# DDS_Module_r1.net
KiCad netlist of a schematic drawn in EAGLE
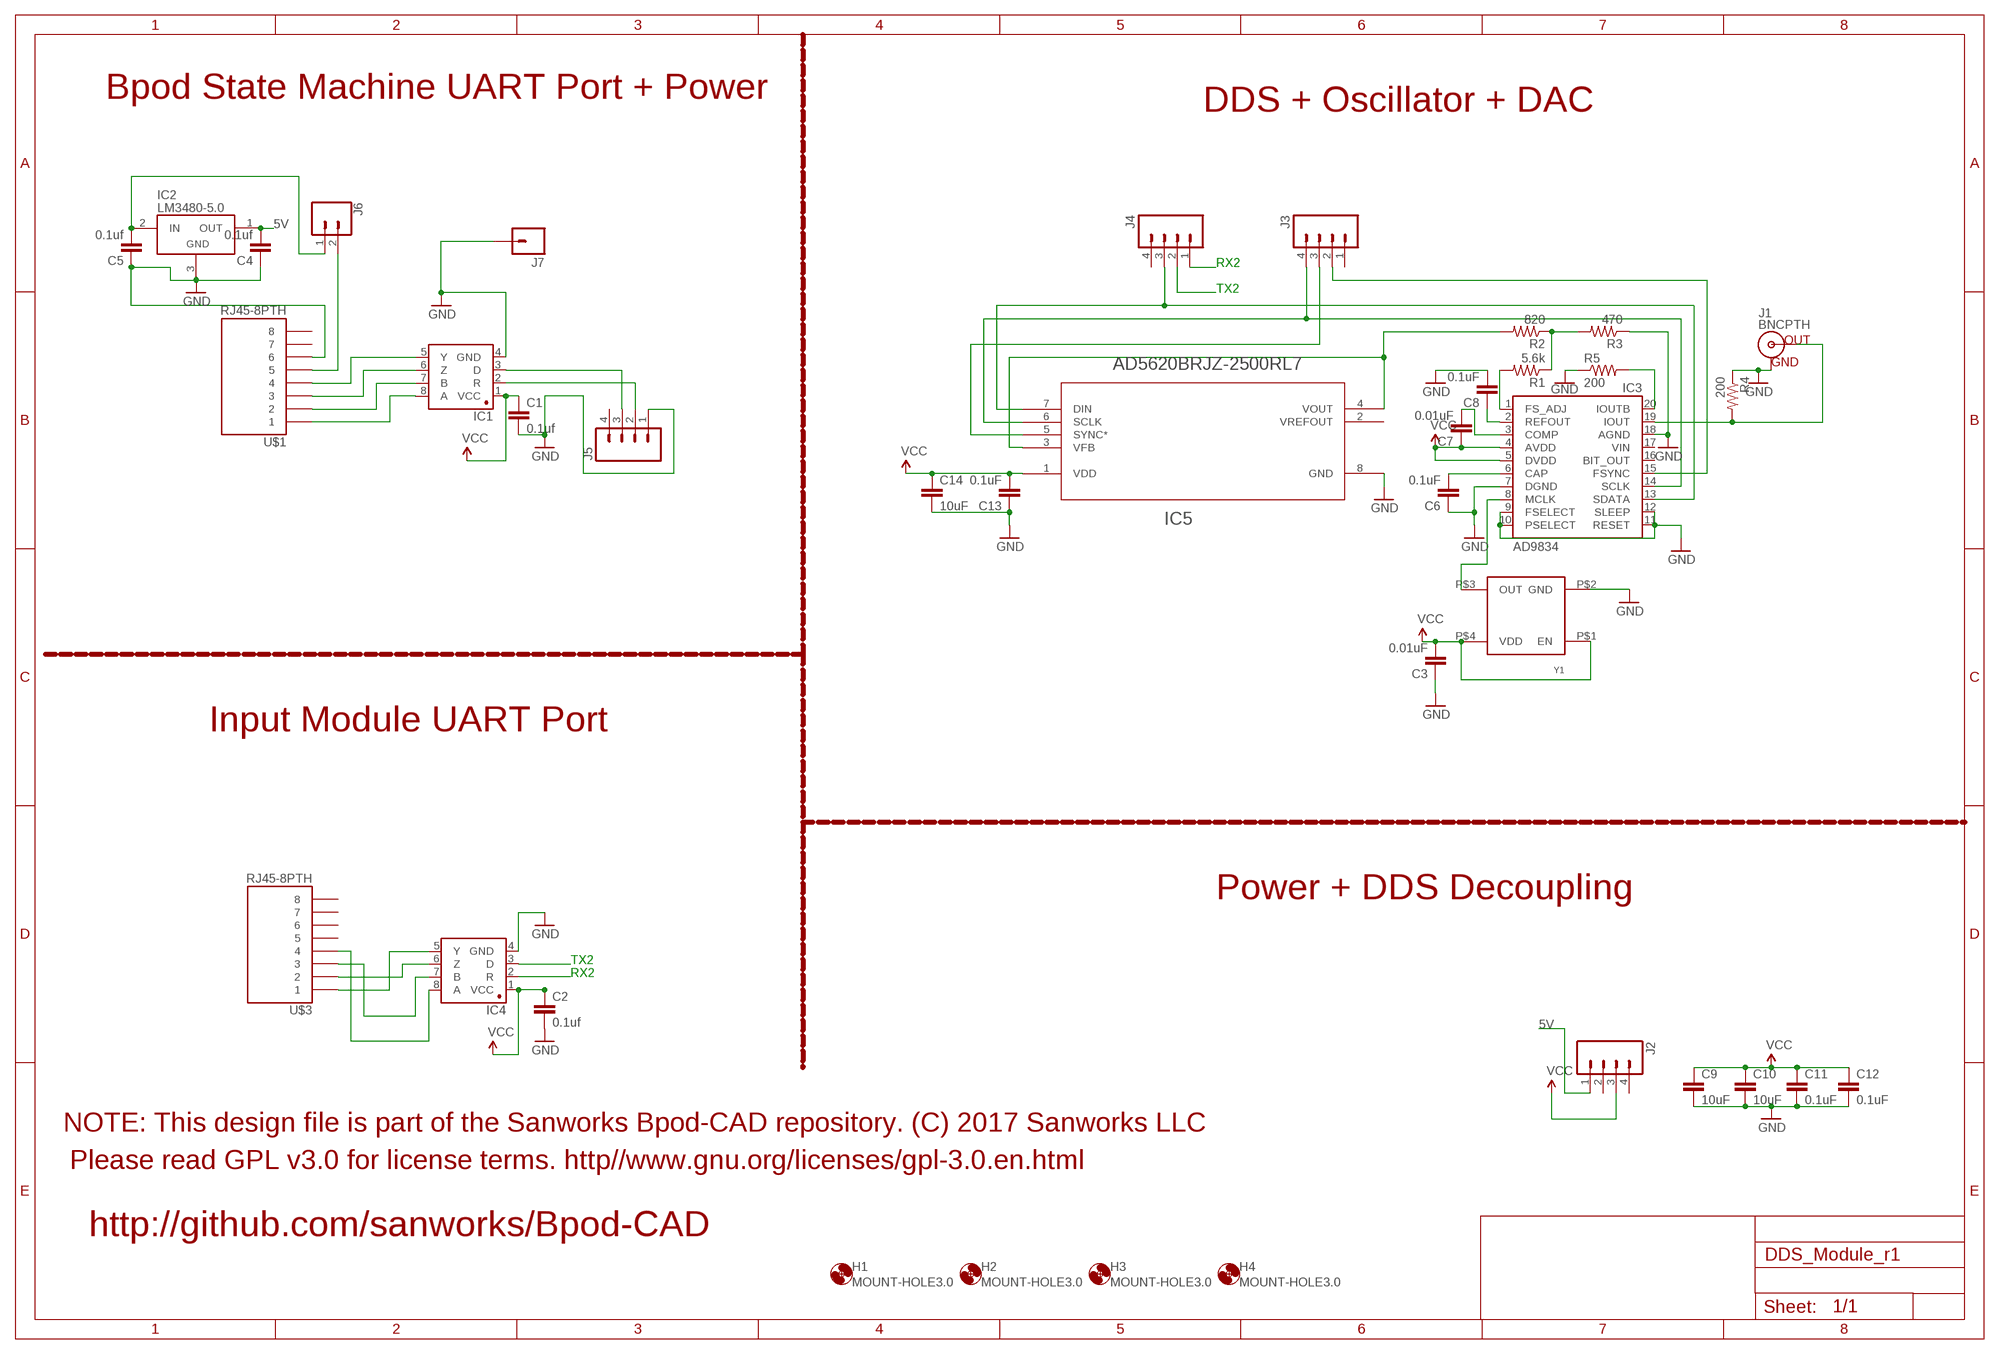
[diagram p0: schematic, sheet 1]

(export (version "E")
  (design (tool "Eeschema 10.0.6"))
  (components
    (comp (ref "C1")
      (value "0.1uf")
      (footprint "eagle-import:1206@1")
      (libsource (lib "eagle-import") (part "CAP1206"))
    )
    (comp (ref "C2")
      (value "0.1uf")
      (footprint "eagle-import:1206@1")
      (libsource (lib "eagle-import") (part "CAP1206"))
    )
    (comp (ref "C3")
      (value "0.01uF")
      (footprint "eagle-import:0805")
      (libsource (lib "eagle-import") (part "10UF-0805-10V-10%"))
    )
    (comp (ref "C4")
      (value "0.1uf")
      (footprint "eagle-import:1206@1")
      (libsource (lib "eagle-import") (part "CAP1206"))
    )
    (comp (ref "C5")
      (value "0.1uf")
      (footprint "eagle-import:1206@1")
      (libsource (lib "eagle-import") (part "CAP1206"))
    )
    (comp (ref "C6")
      (value "0.1uF")
      (footprint "eagle-import:0805")
      (libsource (lib "eagle-import") (part "10UF-0805-10V-10%"))
    )
    (comp (ref "C7")
      (value "0.01uF")
      (footprint "eagle-import:0805")
      (libsource (lib "eagle-import") (part "10UF-0805-10V-10%"))
    )
    (comp (ref "C8")
      (value "0.1uF")
      (footprint "eagle-import:0805")
      (libsource (lib "eagle-import") (part "10UF-0805-10V-10%"))
    )
    (comp (ref "C9")
      (value "10uF")
      (footprint "eagle-import:0805")
      (libsource (lib "eagle-import") (part "10UF-0805-10V-10%"))
    )
    (comp (ref "C10")
      (value "10uF")
      (footprint "eagle-import:0805")
      (libsource (lib "eagle-import") (part "10UF-0805-10V-10%"))
    )
    (comp (ref "C11")
      (value "0.1uF")
      (footprint "eagle-import:0805")
      (libsource (lib "eagle-import") (part "10UF-0805-10V-10%"))
    )
    (comp (ref "C12")
      (value "0.1uF")
      (footprint "eagle-import:0805")
      (libsource (lib "eagle-import") (part "10UF-0805-10V-10%"))
    )
    (comp (ref "C13")
      (value "0.1uF")
      (footprint "eagle-import:0805")
      (libsource (lib "eagle-import") (part "10UF-0805-10V-10%"))
    )
    (comp (ref "C14")
      (value "10uF")
      (footprint "eagle-import:0805")
      (libsource (lib "eagle-import") (part "10UF-0805-10V-10%"))
    )
    (comp (ref "H1")
      (value "MOUNT-HOLE3.0")
      (footprint "eagle-import:3,0")
      (libsource (lib "eagle-import") (part "MOUNT-HOLE3.0"))
    )
    (comp (ref "H2")
      (value "MOUNT-HOLE3.0")
      (footprint "eagle-import:3,0")
      (libsource (lib "eagle-import") (part "MOUNT-HOLE3.0"))
    )
    (comp (ref "H3")
      (value "MOUNT-HOLE3.0")
      (footprint "eagle-import:3,0")
      (libsource (lib "eagle-import") (part "MOUNT-HOLE3.0"))
    )
    (comp (ref "H4")
      (value "MOUNT-HOLE3.0")
      (footprint "eagle-import:3,0")
      (libsource (lib "eagle-import") (part "MOUNT-HOLE3.0"))
    )
    (comp (ref "IC1")
      (value "SN65HVD31DR")
      (footprint "eagle-import:SO08")
      (libsource (lib "eagle-import") (part "SN65HVD31DR"))
    )
    (comp (ref "IC2")
      (value "LM3480-5.0")
      (footprint "eagle-import:SOT-23-3")
      (libsource (lib "eagle-import") (part "LM3480-5.0"))
    )
    (comp (ref "IC3")
      (value "AD9834")
      (footprint "eagle-import:TSSOP20")
      (libsource (lib "eagle-import") (part "AD9834"))
    )
    (comp (ref "IC4")
      (value "SN65HVD31DR")
      (footprint "eagle-import:SO08")
      (libsource (lib "eagle-import") (part "SN65HVD31DR"))
    )
    (comp (ref "IC5")
      (value "AD5620BRJZ-2500RL7")
      (footprint "eagle-import:RJ_8")
      (fields (field (name "MANUFACTURER_PART_NUMBER") "AD5620BRJZ2500RL7"))
      (libsource (lib "eagle-import") (part "AD5620BRJZ-2500RL7"))
    )
    (comp (ref "J1")
      (value "BNCPTH")
      (footprint "eagle-import:BNC")
      (libsource (lib "eagle-import") (part "BNCPTH"))
    )
    (comp (ref "J2")
      (value "M04PTH")
      (footprint "eagle-import:1X04")
      (libsource (lib "eagle-import") (part "M04PTH"))
    )
    (comp (ref "J3")
      (value "M04PTH")
      (footprint "eagle-import:1X04")
      (libsource (lib "eagle-import") (part "M04PTH"))
    )
    (comp (ref "J4")
      (value "M04PTH")
      (footprint "eagle-import:1X04")
      (libsource (lib "eagle-import") (part "M04PTH"))
    )
    (comp (ref "J5")
      (value "M04PTH")
      (footprint "eagle-import:1X04")
      (libsource (lib "eagle-import") (part "M04PTH"))
    )
    (comp (ref "J6")
      (value "CONN_02")
      (footprint "eagle-import:1X02")
      (libsource (lib "eagle-import") (part "CONN_02"))
    )
    (comp (ref "J7")
      (value "M01PTH")
      (footprint "eagle-import:1X01")
      (libsource (lib "eagle-import") (part "M01PTH"))
    )
    (comp (ref "R1")
      (value "5.6k")
      (footprint "eagle-import:R0805")
      (libsource (lib "eagle-import") (part "R-US_R0805"))
    )
    (comp (ref "R2")
      (value "820")
      (footprint "eagle-import:R0805")
      (libsource (lib "eagle-import") (part "R-US_R0805"))
    )
    (comp (ref "R3")
      (value "470")
      (footprint "eagle-import:R0805")
      (libsource (lib "eagle-import") (part "R-US_R0805"))
    )
    (comp (ref "R4")
      (value "200")
      (footprint "eagle-import:R0805")
      (libsource (lib "eagle-import") (part "R-US_R0805"))
    )
    (comp (ref "R5")
      (value "200")
      (footprint "eagle-import:R0805")
      (libsource (lib "eagle-import") (part "R-US_R0805"))
    )
    (comp (ref "U$1")
      (value "RJ45-8PTH")
      (footprint "eagle-import:RJ45-8")
      (libsource (lib "eagle-import") (part "RJ45-8PTH"))
    )
    (comp (ref "U$3")
      (value "RJ45-8PTH")
      (footprint "eagle-import:RJ45-8")
      (libsource (lib "eagle-import") (part "RJ45-8PTH"))
    )
    (comp (ref "Y1")
      (value "ASE10MHZ")
      (footprint "eagle-import:ASE10MHZ")
      (libsource (lib "eagle-import") (part "ASE10MHZ"))
    )
  )
  (nets
    (net (code "1") (name "/5V") (class "Default")
      (node (ref "C4") (pin "2") (pinfunction "2_2") (pintype "passive"))
      (node (ref "IC2") (pin "1") (pinfunction "OUT_1") (pintype "power_in"))
      (node (ref "J2") (pin "1") (pinfunction "1_1") (pintype "passive"))
    )
    (net (code "2") (name "/RX2") (class "Default")
      (node (ref "IC4") (pin "2") (pinfunction "R_2") (pintype "bidirectional"))
      (node (ref "J4") (pin "1") (pinfunction "1_1") (pintype "passive"))
    )
    (net (code "3") (name "/TX2") (class "Default")
      (node (ref "IC4") (pin "3") (pinfunction "D_3") (pintype "bidirectional"))
      (node (ref "J4") (pin "2") (pinfunction "2_2") (pintype "passive"))
    )
    (net (code "4") (name "GND") (class "Default")
      (node (ref "C1") (pin "2") (pinfunction "2_2") (pintype "passive"))
      (node (ref "C10") (pin "2") (pinfunction "2_2") (pintype "passive"))
      (node (ref "C11") (pin "2") (pinfunction "2_2") (pintype "passive"))
      (node (ref "C12") (pin "2") (pinfunction "2_2") (pintype "passive"))
      (node (ref "C13") (pin "1") (pinfunction "1_1") (pintype "passive"))
      (node (ref "C14") (pin "2") (pinfunction "2_2") (pintype "passive"))
      (node (ref "C2") (pin "2") (pinfunction "2_2") (pintype "passive"))
      (node (ref "C3") (pin "1") (pinfunction "1_1") (pintype "passive"))
      (node (ref "C4") (pin "1") (pinfunction "1_1") (pintype "passive"))
      (node (ref "C5") (pin "1") (pinfunction "1_1") (pintype "passive"))
      (node (ref "C6") (pin "1") (pinfunction "1_1") (pintype "passive"))
      (node (ref "C8") (pin "2") (pinfunction "2_2") (pintype "passive"))
      (node (ref "C9") (pin "2") (pinfunction "2_2") (pintype "passive"))
      (node (ref "IC1") (pin "4") (pinfunction "GND_4") (pintype "bidirectional"))
      (node (ref "IC2") (pin "3") (pinfunction "GND_3") (pintype "power_in"))
      (node (ref "IC3") (pin "10") (pinfunction "PSELECT_10") (pintype "bidirectional"))
      (node (ref "IC3") (pin "11") (pinfunction "RESET_11") (pintype "bidirectional"))
      (node (ref "IC3") (pin "12") (pinfunction "SLEEP_12") (pintype "bidirectional"))
      (node (ref "IC3") (pin "18") (pinfunction "AGND_18") (pintype "bidirectional"))
      (node (ref "IC3") (pin "7") (pinfunction "DGND_7") (pintype "bidirectional"))
      (node (ref "IC3") (pin "9") (pinfunction "FSELECT_9") (pintype "bidirectional"))
      (node (ref "IC4") (pin "4") (pinfunction "GND_4") (pintype "bidirectional"))
      (node (ref "IC5") (pin "8") (pinfunction "GND_8") (pintype "passive"))
      (node (ref "J1") (pin "GND") (pinfunction "GND_GND") (pintype "bidirectional"))
      (node (ref "J5") (pin "1") (pinfunction "1_1") (pintype "passive"))
      (node (ref "J7") (pin "1") (pinfunction "1_1") (pintype "passive"))
      (node (ref "R3") (pin "1") (pinfunction "1_1") (pintype "passive"))
      (node (ref "R4") (pin "1") (pinfunction "1_1") (pintype "passive"))
      (node (ref "R5") (pin "1") (pinfunction "1_1") (pintype "passive"))
      (node (ref "U$1") (pin "6") (pinfunction "6_6") (pintype "bidirectional"))
      (node (ref "Y1") (pin "P$2") (pinfunction "GND_P$2") (pintype "bidirectional"))
    )
    (net (code "5") (name "Net-(IC1-A)") (class "Default")
      (node (ref "IC1") (pin "8") (pinfunction "A_8") (pintype "bidirectional"))
      (node (ref "U$1") (pin "1") (pinfunction "1_1") (pintype "bidirectional"))
    )
    (net (code "6") (name "Net-(IC1-B)") (class "Default")
      (node (ref "IC1") (pin "7") (pinfunction "B_7") (pintype "bidirectional"))
      (node (ref "U$1") (pin "2") (pinfunction "2_2") (pintype "bidirectional"))
    )
    (net (code "7") (name "Net-(IC1-D)") (class "Default")
      (node (ref "IC1") (pin "3") (pinfunction "D_3") (pintype "bidirectional"))
      (node (ref "J5") (pin "3") (pinfunction "3_3") (pintype "passive"))
    )
    (net (code "8") (name "Net-(IC1-R)") (class "Default")
      (node (ref "IC1") (pin "2") (pinfunction "R_2") (pintype "bidirectional"))
      (node (ref "J5") (pin "2") (pinfunction "2_2") (pintype "passive"))
    )
    (net (code "9") (name "Net-(IC1-Y)") (class "Default")
      (node (ref "IC1") (pin "5") (pinfunction "Y_5") (pintype "bidirectional"))
      (node (ref "U$1") (pin "4") (pinfunction "4_4") (pintype "bidirectional"))
    )
    (net (code "10") (name "Net-(IC1-Z)") (class "Default")
      (node (ref "IC1") (pin "6") (pinfunction "Z_6") (pintype "bidirectional"))
      (node (ref "U$1") (pin "3") (pinfunction "3_3") (pintype "bidirectional"))
    )
    (net (code "11") (name "Net-(IC2-IN)") (class "Default")
      (node (ref "C5") (pin "2") (pinfunction "2_2") (pintype "passive"))
      (node (ref "IC2") (pin "2") (pinfunction "IN_2") (pintype "power_in"))
      (node (ref "J6") (pin "1") (pinfunction "1_1") (pintype "passive"))
    )
    (net (code "12") (name "Net-(IC3-CAP)") (class "Default")
      (node (ref "C6") (pin "2") (pinfunction "2_2") (pintype "passive"))
      (node (ref "IC3") (pin "6") (pinfunction "CAP_6") (pintype "bidirectional"))
    )
    (net (code "13") (name "Net-(IC3-COMP)") (class "Default")
      (node (ref "C7") (pin "2") (pinfunction "2_2") (pintype "passive"))
      (node (ref "IC3") (pin "3") (pinfunction "COMP_3") (pintype "bidirectional"))
    )
    (net (code "14") (name "Net-(IC3-FSYNC)") (class "Default")
      (node (ref "IC3") (pin "15") (pinfunction "FSYNC_15") (pintype "bidirectional"))
      (node (ref "J3") (pin "2") (pinfunction "2_2") (pintype "passive"))
    )
    (net (code "15") (name "Net-(IC3-FS_ADJ)") (class "Default")
      (node (ref "IC3") (pin "1") (pinfunction "FS_ADJ_1") (pintype "bidirectional"))
      (node (ref "R1") (pin "2") (pinfunction "2_2") (pintype "passive"))
    )
    (net (code "16") (name "Net-(IC3-IOUT)") (class "Default")
      (node (ref "IC3") (pin "19") (pinfunction "IOUT_19") (pintype "bidirectional"))
      (node (ref "J1") (pin "S") (pinfunction "OUT_S") (pintype "bidirectional"))
      (node (ref "R4") (pin "2") (pinfunction "2_2") (pintype "passive"))
    )
    (net (code "17") (name "Net-(IC3-IOUTB)") (class "Default")
      (node (ref "IC3") (pin "20") (pinfunction "IOUTB_20") (pintype "bidirectional"))
      (node (ref "R5") (pin "2") (pinfunction "2_2") (pintype "passive"))
    )
    (net (code "18") (name "Net-(IC3-MCLK)") (class "Default")
      (node (ref "IC3") (pin "8") (pinfunction "MCLK_8") (pintype "bidirectional"))
      (node (ref "Y1") (pin "P$3") (pinfunction "OUT_P$3") (pintype "bidirectional"))
    )
    (net (code "19") (name "Net-(IC3-REFOUT)") (class "Default")
      (node (ref "C8") (pin "1") (pinfunction "1_1") (pintype "passive"))
      (node (ref "IC3") (pin "2") (pinfunction "REFOUT_2") (pintype "bidirectional"))
    )
    (net (code "20") (name "Net-(IC3-SCLK)") (class "Default")
      (node (ref "IC3") (pin "14") (pinfunction "SCLK_14") (pintype "bidirectional"))
      (node (ref "IC5") (pin "6") (pinfunction "SCLK_6") (pintype "passive"))
      (node (ref "J3") (pin "4") (pinfunction "4_4") (pintype "passive"))
    )
    (net (code "21") (name "Net-(IC3-SDATA)") (class "Default")
      (node (ref "IC3") (pin "13") (pinfunction "SDATA_13") (pintype "bidirectional"))
      (node (ref "IC5") (pin "7") (pinfunction "DIN_7") (pintype "passive"))
      (node (ref "J4") (pin "3") (pinfunction "3_3") (pintype "passive"))
    )
    (net (code "22") (name "Net-(IC4-A)") (class "Default")
      (node (ref "IC4") (pin "8") (pinfunction "A_8") (pintype "bidirectional"))
      (node (ref "U$3") (pin "4") (pinfunction "4_4") (pintype "bidirectional"))
    )
    (net (code "23") (name "Net-(IC4-B)") (class "Default")
      (node (ref "IC4") (pin "7") (pinfunction "B_7") (pintype "bidirectional"))
      (node (ref "U$3") (pin "3") (pinfunction "3_3") (pintype "bidirectional"))
    )
    (net (code "24") (name "Net-(IC4-Y)") (class "Default")
      (node (ref "IC4") (pin "5") (pinfunction "Y_5") (pintype "bidirectional"))
      (node (ref "U$3") (pin "1") (pinfunction "1_1") (pintype "bidirectional"))
    )
    (net (code "25") (name "Net-(IC4-Z)") (class "Default")
      (node (ref "IC4") (pin "6") (pinfunction "Z_6") (pintype "bidirectional"))
      (node (ref "U$3") (pin "2") (pinfunction "2_2") (pintype "bidirectional"))
    )
    (net (code "26") (name "Net-(IC5-SYNC*)") (class "Default")
      (node (ref "IC5") (pin "5") (pinfunction "SYNC*_5") (pintype "passive"))
      (node (ref "J3") (pin "3") (pinfunction "3_3") (pintype "passive"))
    )
    (net (code "27") (name "Net-(IC5-VFB)") (class "Default")
      (node (ref "IC5") (pin "3") (pinfunction "VFB_3") (pintype "passive"))
      (node (ref "IC5") (pin "4") (pinfunction "VOUT_4") (pintype "passive"))
      (node (ref "R2") (pin "2") (pinfunction "2_2") (pintype "passive"))
    )
    (net (code "28") (name "Net-(J6-Pad2)") (class "Default")
      (node (ref "J6") (pin "2") (pinfunction "2_2") (pintype "passive"))
      (node (ref "U$1") (pin "5") (pinfunction "5_5") (pintype "bidirectional"))
    )
    (net (code "29") (name "Net-(R1-Pad1)") (class "Default")
      (node (ref "R1") (pin "1") (pinfunction "1_1") (pintype "passive"))
      (node (ref "R2") (pin "1") (pinfunction "1_1") (pintype "passive"))
      (node (ref "R3") (pin "2") (pinfunction "2_2") (pintype "passive"))
    )
    (net (code "30") (name "VCC") (class "Default")
      (node (ref "C1") (pin "1") (pinfunction "1_1") (pintype "passive"))
      (node (ref "C10") (pin "1") (pinfunction "1_1") (pintype "passive"))
      (node (ref "C11") (pin "1") (pinfunction "1_1") (pintype "passive"))
      (node (ref "C12") (pin "1") (pinfunction "1_1") (pintype "passive"))
      (node (ref "C13") (pin "2") (pinfunction "2_2") (pintype "passive"))
      (node (ref "C14") (pin "1") (pinfunction "1_1") (pintype "passive"))
      (node (ref "C2") (pin "1") (pinfunction "1_1") (pintype "passive"))
      (node (ref "C3") (pin "2") (pinfunction "2_2") (pintype "passive"))
      (node (ref "C7") (pin "1") (pinfunction "1_1") (pintype "passive"))
      (node (ref "C9") (pin "1") (pinfunction "1_1") (pintype "passive"))
      (node (ref "IC1") (pin "1") (pinfunction "VCC_1") (pintype "bidirectional"))
      (node (ref "IC3") (pin "4") (pinfunction "AVDD_4") (pintype "bidirectional"))
      (node (ref "IC3") (pin "5") (pinfunction "DVDD_5") (pintype "bidirectional"))
      (node (ref "IC4") (pin "1") (pinfunction "VCC_1") (pintype "bidirectional"))
      (node (ref "IC5") (pin "1") (pinfunction "VDD_1") (pintype "power_in"))
      (node (ref "J2") (pin "3") (pinfunction "3_3") (pintype "passive"))
      (node (ref "Y1") (pin "P$1") (pinfunction "EN_P$1") (pintype "bidirectional"))
      (node (ref "Y1") (pin "P$4") (pinfunction "VDD_P$4") (pintype "bidirectional"))
    )
    (net (code "31") (name "unconnected-(IC3-BIT_OUT-Pad16)") (class "Default")
      (node (ref "IC3") (pin "16") (pinfunction "BIT_OUT_16") (pintype "bidirectional"))
    )
    (net (code "32") (name "unconnected-(IC3-VIN-Pad17)") (class "Default")
      (node (ref "IC3") (pin "17") (pinfunction "VIN_17") (pintype "bidirectional"))
    )
    (net (code "33") (name "unconnected-(IC5-VREFOUT-Pad2)") (class "Default")
      (node (ref "IC5") (pin "2") (pinfunction "VREFOUT_2") (pintype "passive"))
    )
    (net (code "34") (name "unconnected-(J2-Pad2)") (class "Default")
      (node (ref "J2") (pin "2") (pinfunction "2_2") (pintype "passive"))
    )
    (net (code "35") (name "unconnected-(J2-Pad4)") (class "Default")
      (node (ref "J2") (pin "4") (pinfunction "4_4") (pintype "passive"))
    )
    (net (code "36") (name "unconnected-(J3-Pad1)") (class "Default")
      (node (ref "J3") (pin "1") (pinfunction "1_1") (pintype "passive"))
    )
    (net (code "37") (name "unconnected-(J4-Pad4)") (class "Default")
      (node (ref "J4") (pin "4") (pinfunction "4_4") (pintype "passive"))
    )
    (net (code "38") (name "unconnected-(J5-Pad4)") (class "Default")
      (node (ref "J5") (pin "4") (pinfunction "4_4") (pintype "passive"))
    )
    (net (code "39") (name "unconnected-(U$1-Pad7)") (class "Default")
      (node (ref "U$1") (pin "7") (pinfunction "7_7") (pintype "bidirectional"))
    )
    (net (code "40") (name "unconnected-(U$1-Pad8)") (class "Default")
      (node (ref "U$1") (pin "8") (pinfunction "8_8") (pintype "bidirectional"))
    )
    (net (code "41") (name "unconnected-(U$3-Pad5)") (class "Default")
      (node (ref "U$3") (pin "5") (pinfunction "5_5") (pintype "bidirectional"))
    )
    (net (code "42") (name "unconnected-(U$3-Pad6)") (class "Default")
      (node (ref "U$3") (pin "6") (pinfunction "6_6") (pintype "bidirectional"))
    )
    (net (code "43") (name "unconnected-(U$3-Pad7)") (class "Default")
      (node (ref "U$3") (pin "7") (pinfunction "7_7") (pintype "bidirectional"))
    )
    (net (code "44") (name "unconnected-(U$3-Pad8)") (class "Default")
      (node (ref "U$3") (pin "8") (pinfunction "8_8") (pintype "bidirectional"))
    )
  )
)
